# MATRIXMODULE.net
KiCad netlist of a schematic drawn in EAGLE
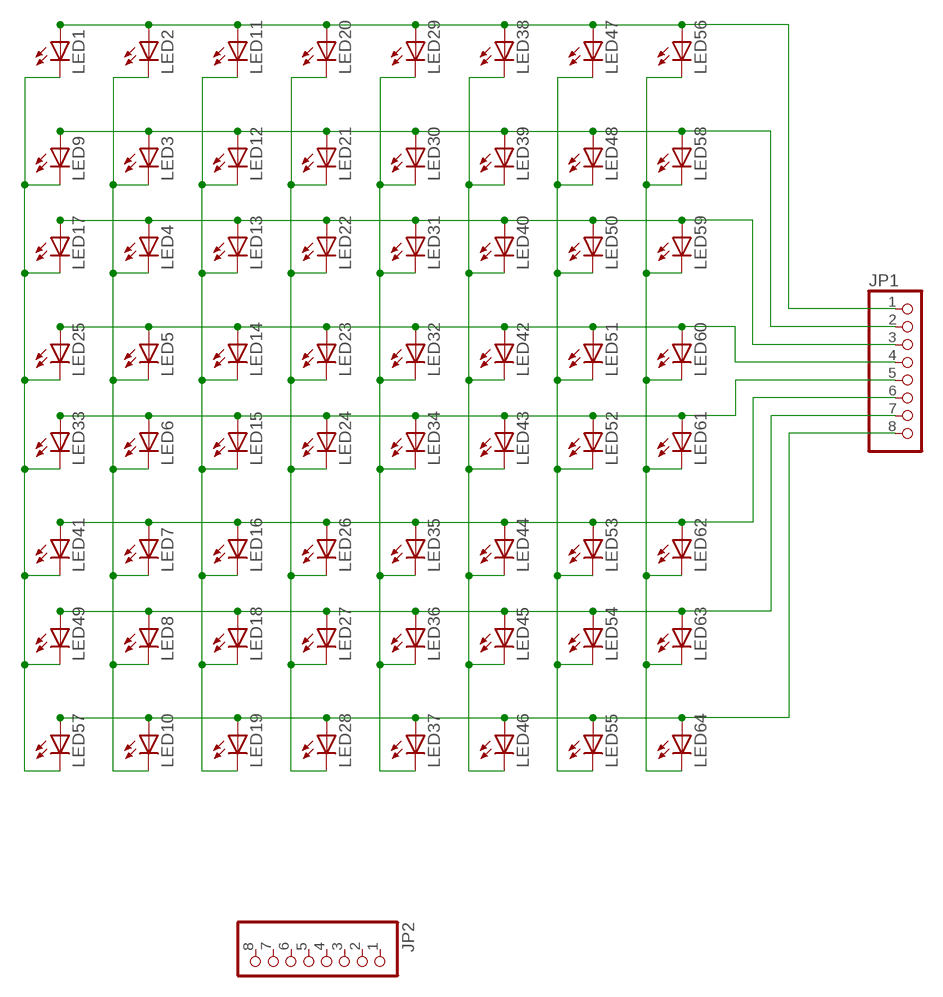
[diagram p0: schematic, sheet 1]

(export (version "E")
  (design (tool "Eeschema 10.0.6"))
  (components
    (comp (ref "JP1")
      (value "PINHD-1X8CLEANBIG")
      (footprint "eagle-import:1X08-CLEANBIG")
      (libsource (lib "eagle-import") (part "PINHD-1X8CLEANBIG"))
    )
    (comp (ref "JP2")
      (value "PINHD-1X8CLEANBIG")
      (footprint "eagle-import:1X08-CLEANBIG")
      (libsource (lib "eagle-import") (part "PINHD-1X8CLEANBIG"))
    )
    (comp (ref "LED1")
      (value "LED5MM")
      (footprint "eagle-import:LED5MM")
      (libsource (lib "eagle-import") (part "LED5MM"))
    )
    (comp (ref "LED2")
      (value "LED5MM")
      (footprint "eagle-import:LED5MM")
      (libsource (lib "eagle-import") (part "LED5MM"))
    )
    (comp (ref "LED3")
      (value "LED5MM")
      (footprint "eagle-import:LED5MM")
      (libsource (lib "eagle-import") (part "LED5MM"))
    )
    (comp (ref "LED4")
      (value "LED5MM")
      (footprint "eagle-import:LED5MM")
      (libsource (lib "eagle-import") (part "LED5MM"))
    )
    (comp (ref "LED5")
      (value "LED5MM")
      (footprint "eagle-import:LED5MM")
      (libsource (lib "eagle-import") (part "LED5MM"))
    )
    (comp (ref "LED6")
      (value "LED5MM")
      (footprint "eagle-import:LED5MM")
      (libsource (lib "eagle-import") (part "LED5MM"))
    )
    (comp (ref "LED7")
      (value "LED5MM")
      (footprint "eagle-import:LED5MM")
      (libsource (lib "eagle-import") (part "LED5MM"))
    )
    (comp (ref "LED8")
      (value "LED5MM")
      (footprint "eagle-import:LED5MM")
      (libsource (lib "eagle-import") (part "LED5MM"))
    )
    (comp (ref "LED9")
      (value "LED5MM")
      (footprint "eagle-import:LED5MM")
      (libsource (lib "eagle-import") (part "LED5MM"))
    )
    (comp (ref "LED10")
      (value "LED5MM")
      (footprint "eagle-import:LED5MM")
      (libsource (lib "eagle-import") (part "LED5MM"))
    )
    (comp (ref "LED11")
      (value "LED5MM")
      (footprint "eagle-import:LED5MM")
      (libsource (lib "eagle-import") (part "LED5MM"))
    )
    (comp (ref "LED12")
      (value "LED5MM")
      (footprint "eagle-import:LED5MM")
      (libsource (lib "eagle-import") (part "LED5MM"))
    )
    (comp (ref "LED13")
      (value "LED5MM")
      (footprint "eagle-import:LED5MM")
      (libsource (lib "eagle-import") (part "LED5MM"))
    )
    (comp (ref "LED14")
      (value "LED5MM")
      (footprint "eagle-import:LED5MM")
      (libsource (lib "eagle-import") (part "LED5MM"))
    )
    (comp (ref "LED15")
      (value "LED5MM")
      (footprint "eagle-import:LED5MM")
      (libsource (lib "eagle-import") (part "LED5MM"))
    )
    (comp (ref "LED16")
      (value "LED5MM")
      (footprint "eagle-import:LED5MM")
      (libsource (lib "eagle-import") (part "LED5MM"))
    )
    (comp (ref "LED17")
      (value "LED5MM")
      (footprint "eagle-import:LED5MM")
      (libsource (lib "eagle-import") (part "LED5MM"))
    )
    (comp (ref "LED18")
      (value "LED5MM")
      (footprint "eagle-import:LED5MM")
      (libsource (lib "eagle-import") (part "LED5MM"))
    )
    (comp (ref "LED19")
      (value "LED5MM")
      (footprint "eagle-import:LED5MM")
      (libsource (lib "eagle-import") (part "LED5MM"))
    )
    (comp (ref "LED20")
      (value "LED5MM")
      (footprint "eagle-import:LED5MM")
      (libsource (lib "eagle-import") (part "LED5MM"))
    )
    (comp (ref "LED21")
      (value "LED5MM")
      (footprint "eagle-import:LED5MM")
      (libsource (lib "eagle-import") (part "LED5MM"))
    )
    (comp (ref "LED22")
      (value "LED5MM")
      (footprint "eagle-import:LED5MM")
      (libsource (lib "eagle-import") (part "LED5MM"))
    )
    (comp (ref "LED23")
      (value "LED5MM")
      (footprint "eagle-import:LED5MM")
      (libsource (lib "eagle-import") (part "LED5MM"))
    )
    (comp (ref "LED24")
      (value "LED5MM")
      (footprint "eagle-import:LED5MM")
      (libsource (lib "eagle-import") (part "LED5MM"))
    )
    (comp (ref "LED25")
      (value "LED5MM")
      (footprint "eagle-import:LED5MM")
      (libsource (lib "eagle-import") (part "LED5MM"))
    )
    (comp (ref "LED26")
      (value "LED5MM")
      (footprint "eagle-import:LED5MM")
      (libsource (lib "eagle-import") (part "LED5MM"))
    )
    (comp (ref "LED27")
      (value "LED5MM")
      (footprint "eagle-import:LED5MM")
      (libsource (lib "eagle-import") (part "LED5MM"))
    )
    (comp (ref "LED28")
      (value "LED5MM")
      (footprint "eagle-import:LED5MM")
      (libsource (lib "eagle-import") (part "LED5MM"))
    )
    (comp (ref "LED29")
      (value "LED5MM")
      (footprint "eagle-import:LED5MM")
      (libsource (lib "eagle-import") (part "LED5MM"))
    )
    (comp (ref "LED30")
      (value "LED5MM")
      (footprint "eagle-import:LED5MM")
      (libsource (lib "eagle-import") (part "LED5MM"))
    )
    (comp (ref "LED31")
      (value "LED5MM")
      (footprint "eagle-import:LED5MM")
      (libsource (lib "eagle-import") (part "LED5MM"))
    )
    (comp (ref "LED32")
      (value "LED5MM")
      (footprint "eagle-import:LED5MM")
      (libsource (lib "eagle-import") (part "LED5MM"))
    )
    (comp (ref "LED33")
      (value "LED5MM")
      (footprint "eagle-import:LED5MM")
      (libsource (lib "eagle-import") (part "LED5MM"))
    )
    (comp (ref "LED34")
      (value "LED5MM")
      (footprint "eagle-import:LED5MM")
      (libsource (lib "eagle-import") (part "LED5MM"))
    )
    (comp (ref "LED35")
      (value "LED5MM")
      (footprint "eagle-import:LED5MM")
      (libsource (lib "eagle-import") (part "LED5MM"))
    )
    (comp (ref "LED36")
      (value "LED5MM")
      (footprint "eagle-import:LED5MM")
      (libsource (lib "eagle-import") (part "LED5MM"))
    )
    (comp (ref "LED37")
      (value "LED5MM")
      (footprint "eagle-import:LED5MM")
      (libsource (lib "eagle-import") (part "LED5MM"))
    )
    (comp (ref "LED38")
      (value "LED5MM")
      (footprint "eagle-import:LED5MM")
      (libsource (lib "eagle-import") (part "LED5MM"))
    )
    (comp (ref "LED39")
      (value "LED5MM")
      (footprint "eagle-import:LED5MM")
      (libsource (lib "eagle-import") (part "LED5MM"))
    )
    (comp (ref "LED40")
      (value "LED5MM")
      (footprint "eagle-import:LED5MM")
      (libsource (lib "eagle-import") (part "LED5MM"))
    )
    (comp (ref "LED41")
      (value "LED5MM")
      (footprint "eagle-import:LED5MM")
      (libsource (lib "eagle-import") (part "LED5MM"))
    )
    (comp (ref "LED42")
      (value "LED5MM")
      (footprint "eagle-import:LED5MM")
      (libsource (lib "eagle-import") (part "LED5MM"))
    )
    (comp (ref "LED43")
      (value "LED5MM")
      (footprint "eagle-import:LED5MM")
      (libsource (lib "eagle-import") (part "LED5MM"))
    )
    (comp (ref "LED44")
      (value "LED5MM")
      (footprint "eagle-import:LED5MM")
      (libsource (lib "eagle-import") (part "LED5MM"))
    )
    (comp (ref "LED45")
      (value "LED5MM")
      (footprint "eagle-import:LED5MM")
      (libsource (lib "eagle-import") (part "LED5MM"))
    )
    (comp (ref "LED46")
      (value "LED5MM")
      (footprint "eagle-import:LED5MM")
      (libsource (lib "eagle-import") (part "LED5MM"))
    )
    (comp (ref "LED47")
      (value "LED5MM")
      (footprint "eagle-import:LED5MM")
      (libsource (lib "eagle-import") (part "LED5MM"))
    )
    (comp (ref "LED48")
      (value "LED5MM")
      (footprint "eagle-import:LED5MM")
      (libsource (lib "eagle-import") (part "LED5MM"))
    )
    (comp (ref "LED49")
      (value "LED5MM")
      (footprint "eagle-import:LED5MM")
      (libsource (lib "eagle-import") (part "LED5MM"))
    )
    (comp (ref "LED50")
      (value "LED5MM")
      (footprint "eagle-import:LED5MM")
      (libsource (lib "eagle-import") (part "LED5MM"))
    )
    (comp (ref "LED51")
      (value "LED5MM")
      (footprint "eagle-import:LED5MM")
      (libsource (lib "eagle-import") (part "LED5MM"))
    )
    (comp (ref "LED52")
      (value "LED5MM")
      (footprint "eagle-import:LED5MM")
      (libsource (lib "eagle-import") (part "LED5MM"))
    )
    (comp (ref "LED53")
      (value "LED5MM")
      (footprint "eagle-import:LED5MM")
      (libsource (lib "eagle-import") (part "LED5MM"))
    )
    (comp (ref "LED54")
      (value "LED5MM")
      (footprint "eagle-import:LED5MM")
      (libsource (lib "eagle-import") (part "LED5MM"))
    )
    (comp (ref "LED55")
      (value "LED5MM")
      (footprint "eagle-import:LED5MM")
      (libsource (lib "eagle-import") (part "LED5MM"))
    )
    (comp (ref "LED56")
      (value "LED5MM")
      (footprint "eagle-import:LED5MM")
      (libsource (lib "eagle-import") (part "LED5MM"))
    )
    (comp (ref "LED57")
      (value "LED5MM")
      (footprint "eagle-import:LED5MM")
      (libsource (lib "eagle-import") (part "LED5MM"))
    )
    (comp (ref "LED58")
      (value "LED5MM")
      (footprint "eagle-import:LED5MM")
      (libsource (lib "eagle-import") (part "LED5MM"))
    )
    (comp (ref "LED59")
      (value "LED5MM")
      (footprint "eagle-import:LED5MM")
      (libsource (lib "eagle-import") (part "LED5MM"))
    )
    (comp (ref "LED60")
      (value "LED5MM")
      (footprint "eagle-import:LED5MM")
      (libsource (lib "eagle-import") (part "LED5MM"))
    )
    (comp (ref "LED61")
      (value "LED5MM")
      (footprint "eagle-import:LED5MM")
      (libsource (lib "eagle-import") (part "LED5MM"))
    )
    (comp (ref "LED62")
      (value "LED5MM")
      (footprint "eagle-import:LED5MM")
      (libsource (lib "eagle-import") (part "LED5MM"))
    )
    (comp (ref "LED63")
      (value "LED5MM")
      (footprint "eagle-import:LED5MM")
      (libsource (lib "eagle-import") (part "LED5MM"))
    )
    (comp (ref "LED64")
      (value "LED5MM")
      (footprint "eagle-import:LED5MM")
      (libsource (lib "eagle-import") (part "LED5MM"))
    )
  )
  (nets
    (net (code "1") (name "Net-(JP1-Pad1)") (class "Default")
      (node (ref "JP1") (pin "1") (pinfunction "1_1") (pintype "passive"))
      (node (ref "LED1") (pin "A") (pinfunction "A_A") (pintype "passive"))
      (node (ref "LED11") (pin "A") (pinfunction "A_A") (pintype "passive"))
      (node (ref "LED2") (pin "A") (pinfunction "A_A") (pintype "passive"))
      (node (ref "LED20") (pin "A") (pinfunction "A_A") (pintype "passive"))
      (node (ref "LED29") (pin "A") (pinfunction "A_A") (pintype "passive"))
      (node (ref "LED38") (pin "A") (pinfunction "A_A") (pintype "passive"))
      (node (ref "LED47") (pin "A") (pinfunction "A_A") (pintype "passive"))
      (node (ref "LED56") (pin "A") (pinfunction "A_A") (pintype "passive"))
    )
    (net (code "2") (name "Net-(JP1-Pad2)") (class "Default")
      (node (ref "JP1") (pin "2") (pinfunction "2_2") (pintype "passive"))
      (node (ref "LED12") (pin "A") (pinfunction "A_A") (pintype "passive"))
      (node (ref "LED21") (pin "A") (pinfunction "A_A") (pintype "passive"))
      (node (ref "LED3") (pin "A") (pinfunction "A_A") (pintype "passive"))
      (node (ref "LED30") (pin "A") (pinfunction "A_A") (pintype "passive"))
      (node (ref "LED39") (pin "A") (pinfunction "A_A") (pintype "passive"))
      (node (ref "LED48") (pin "A") (pinfunction "A_A") (pintype "passive"))
      (node (ref "LED58") (pin "A") (pinfunction "A_A") (pintype "passive"))
      (node (ref "LED9") (pin "A") (pinfunction "A_A") (pintype "passive"))
    )
    (net (code "3") (name "Net-(JP1-Pad3)") (class "Default")
      (node (ref "JP1") (pin "3") (pinfunction "3_3") (pintype "passive"))
      (node (ref "LED13") (pin "A") (pinfunction "A_A") (pintype "passive"))
      (node (ref "LED17") (pin "A") (pinfunction "A_A") (pintype "passive"))
      (node (ref "LED22") (pin "A") (pinfunction "A_A") (pintype "passive"))
      (node (ref "LED31") (pin "A") (pinfunction "A_A") (pintype "passive"))
      (node (ref "LED4") (pin "A") (pinfunction "A_A") (pintype "passive"))
      (node (ref "LED40") (pin "A") (pinfunction "A_A") (pintype "passive"))
      (node (ref "LED50") (pin "A") (pinfunction "A_A") (pintype "passive"))
      (node (ref "LED59") (pin "A") (pinfunction "A_A") (pintype "passive"))
    )
    (net (code "4") (name "Net-(JP1-Pad4)") (class "Default")
      (node (ref "JP1") (pin "4") (pinfunction "4_4") (pintype "passive"))
      (node (ref "LED14") (pin "A") (pinfunction "A_A") (pintype "passive"))
      (node (ref "LED23") (pin "A") (pinfunction "A_A") (pintype "passive"))
      (node (ref "LED25") (pin "A") (pinfunction "A_A") (pintype "passive"))
      (node (ref "LED32") (pin "A") (pinfunction "A_A") (pintype "passive"))
      (node (ref "LED42") (pin "A") (pinfunction "A_A") (pintype "passive"))
      (node (ref "LED5") (pin "A") (pinfunction "A_A") (pintype "passive"))
      (node (ref "LED51") (pin "A") (pinfunction "A_A") (pintype "passive"))
      (node (ref "LED60") (pin "A") (pinfunction "A_A") (pintype "passive"))
    )
    (net (code "5") (name "Net-(JP1-Pad5)") (class "Default")
      (node (ref "JP1") (pin "5") (pinfunction "5_5") (pintype "passive"))
      (node (ref "LED15") (pin "A") (pinfunction "A_A") (pintype "passive"))
      (node (ref "LED24") (pin "A") (pinfunction "A_A") (pintype "passive"))
      (node (ref "LED33") (pin "A") (pinfunction "A_A") (pintype "passive"))
      (node (ref "LED34") (pin "A") (pinfunction "A_A") (pintype "passive"))
      (node (ref "LED43") (pin "A") (pinfunction "A_A") (pintype "passive"))
      (node (ref "LED52") (pin "A") (pinfunction "A_A") (pintype "passive"))
      (node (ref "LED6") (pin "A") (pinfunction "A_A") (pintype "passive"))
      (node (ref "LED61") (pin "A") (pinfunction "A_A") (pintype "passive"))
    )
    (net (code "6") (name "Net-(JP1-Pad6)") (class "Default")
      (node (ref "JP1") (pin "6") (pinfunction "6_6") (pintype "passive"))
      (node (ref "LED16") (pin "A") (pinfunction "A_A") (pintype "passive"))
      (node (ref "LED26") (pin "A") (pinfunction "A_A") (pintype "passive"))
      (node (ref "LED35") (pin "A") (pinfunction "A_A") (pintype "passive"))
      (node (ref "LED41") (pin "A") (pinfunction "A_A") (pintype "passive"))
      (node (ref "LED44") (pin "A") (pinfunction "A_A") (pintype "passive"))
      (node (ref "LED53") (pin "A") (pinfunction "A_A") (pintype "passive"))
      (node (ref "LED62") (pin "A") (pinfunction "A_A") (pintype "passive"))
      (node (ref "LED7") (pin "A") (pinfunction "A_A") (pintype "passive"))
    )
    (net (code "7") (name "Net-(JP1-Pad7)") (class "Default")
      (node (ref "JP1") (pin "7") (pinfunction "7_7") (pintype "passive"))
      (node (ref "LED18") (pin "A") (pinfunction "A_A") (pintype "passive"))
      (node (ref "LED27") (pin "A") (pinfunction "A_A") (pintype "passive"))
      (node (ref "LED36") (pin "A") (pinfunction "A_A") (pintype "passive"))
      (node (ref "LED45") (pin "A") (pinfunction "A_A") (pintype "passive"))
      (node (ref "LED49") (pin "A") (pinfunction "A_A") (pintype "passive"))
      (node (ref "LED54") (pin "A") (pinfunction "A_A") (pintype "passive"))
      (node (ref "LED63") (pin "A") (pinfunction "A_A") (pintype "passive"))
      (node (ref "LED8") (pin "A") (pinfunction "A_A") (pintype "passive"))
    )
    (net (code "8") (name "Net-(JP1-Pad8)") (class "Default")
      (node (ref "JP1") (pin "8") (pinfunction "8_8") (pintype "passive"))
      (node (ref "LED10") (pin "A") (pinfunction "A_A") (pintype "passive"))
      (node (ref "LED19") (pin "A") (pinfunction "A_A") (pintype "passive"))
      (node (ref "LED28") (pin "A") (pinfunction "A_A") (pintype "passive"))
      (node (ref "LED37") (pin "A") (pinfunction "A_A") (pintype "passive"))
      (node (ref "LED46") (pin "A") (pinfunction "A_A") (pintype "passive"))
      (node (ref "LED55") (pin "A") (pinfunction "A_A") (pintype "passive"))
      (node (ref "LED57") (pin "A") (pinfunction "A_A") (pintype "passive"))
      (node (ref "LED64") (pin "A") (pinfunction "A_A") (pintype "passive"))
    )
    (net (code "9") (name "Net-(LED1-C)") (class "Default")
      (node (ref "LED1") (pin "K") (pinfunction "C_K") (pintype "passive"))
      (node (ref "LED17") (pin "K") (pinfunction "C_K") (pintype "passive"))
      (node (ref "LED25") (pin "K") (pinfunction "C_K") (pintype "passive"))
      (node (ref "LED33") (pin "K") (pinfunction "C_K") (pintype "passive"))
      (node (ref "LED41") (pin "K") (pinfunction "C_K") (pintype "passive"))
      (node (ref "LED49") (pin "K") (pinfunction "C_K") (pintype "passive"))
      (node (ref "LED57") (pin "K") (pinfunction "C_K") (pintype "passive"))
      (node (ref "LED9") (pin "K") (pinfunction "C_K") (pintype "passive"))
    )
    (net (code "10") (name "Net-(LED10-C)") (class "Default")
      (node (ref "LED10") (pin "K") (pinfunction "C_K") (pintype "passive"))
      (node (ref "LED2") (pin "K") (pinfunction "C_K") (pintype "passive"))
      (node (ref "LED3") (pin "K") (pinfunction "C_K") (pintype "passive"))
      (node (ref "LED4") (pin "K") (pinfunction "C_K") (pintype "passive"))
      (node (ref "LED5") (pin "K") (pinfunction "C_K") (pintype "passive"))
      (node (ref "LED6") (pin "K") (pinfunction "C_K") (pintype "passive"))
      (node (ref "LED7") (pin "K") (pinfunction "C_K") (pintype "passive"))
      (node (ref "LED8") (pin "K") (pinfunction "C_K") (pintype "passive"))
    )
    (net (code "11") (name "Net-(LED11-C)") (class "Default")
      (node (ref "LED11") (pin "K") (pinfunction "C_K") (pintype "passive"))
      (node (ref "LED12") (pin "K") (pinfunction "C_K") (pintype "passive"))
      (node (ref "LED13") (pin "K") (pinfunction "C_K") (pintype "passive"))
      (node (ref "LED14") (pin "K") (pinfunction "C_K") (pintype "passive"))
      (node (ref "LED15") (pin "K") (pinfunction "C_K") (pintype "passive"))
      (node (ref "LED16") (pin "K") (pinfunction "C_K") (pintype "passive"))
      (node (ref "LED18") (pin "K") (pinfunction "C_K") (pintype "passive"))
      (node (ref "LED19") (pin "K") (pinfunction "C_K") (pintype "passive"))
    )
    (net (code "12") (name "Net-(LED20-C)") (class "Default")
      (node (ref "LED20") (pin "K") (pinfunction "C_K") (pintype "passive"))
      (node (ref "LED21") (pin "K") (pinfunction "C_K") (pintype "passive"))
      (node (ref "LED22") (pin "K") (pinfunction "C_K") (pintype "passive"))
      (node (ref "LED23") (pin "K") (pinfunction "C_K") (pintype "passive"))
      (node (ref "LED24") (pin "K") (pinfunction "C_K") (pintype "passive"))
      (node (ref "LED26") (pin "K") (pinfunction "C_K") (pintype "passive"))
      (node (ref "LED27") (pin "K") (pinfunction "C_K") (pintype "passive"))
      (node (ref "LED28") (pin "K") (pinfunction "C_K") (pintype "passive"))
    )
    (net (code "13") (name "Net-(LED29-C)") (class "Default")
      (node (ref "LED29") (pin "K") (pinfunction "C_K") (pintype "passive"))
      (node (ref "LED30") (pin "K") (pinfunction "C_K") (pintype "passive"))
      (node (ref "LED31") (pin "K") (pinfunction "C_K") (pintype "passive"))
      (node (ref "LED32") (pin "K") (pinfunction "C_K") (pintype "passive"))
      (node (ref "LED34") (pin "K") (pinfunction "C_K") (pintype "passive"))
      (node (ref "LED35") (pin "K") (pinfunction "C_K") (pintype "passive"))
      (node (ref "LED36") (pin "K") (pinfunction "C_K") (pintype "passive"))
      (node (ref "LED37") (pin "K") (pinfunction "C_K") (pintype "passive"))
    )
    (net (code "14") (name "Net-(LED38-C)") (class "Default")
      (node (ref "LED38") (pin "K") (pinfunction "C_K") (pintype "passive"))
      (node (ref "LED39") (pin "K") (pinfunction "C_K") (pintype "passive"))
      (node (ref "LED40") (pin "K") (pinfunction "C_K") (pintype "passive"))
      (node (ref "LED42") (pin "K") (pinfunction "C_K") (pintype "passive"))
      (node (ref "LED43") (pin "K") (pinfunction "C_K") (pintype "passive"))
      (node (ref "LED44") (pin "K") (pinfunction "C_K") (pintype "passive"))
      (node (ref "LED45") (pin "K") (pinfunction "C_K") (pintype "passive"))
      (node (ref "LED46") (pin "K") (pinfunction "C_K") (pintype "passive"))
    )
    (net (code "15") (name "Net-(LED47-C)") (class "Default")
      (node (ref "LED47") (pin "K") (pinfunction "C_K") (pintype "passive"))
      (node (ref "LED48") (pin "K") (pinfunction "C_K") (pintype "passive"))
      (node (ref "LED50") (pin "K") (pinfunction "C_K") (pintype "passive"))
      (node (ref "LED51") (pin "K") (pinfunction "C_K") (pintype "passive"))
      (node (ref "LED52") (pin "K") (pinfunction "C_K") (pintype "passive"))
      (node (ref "LED53") (pin "K") (pinfunction "C_K") (pintype "passive"))
      (node (ref "LED54") (pin "K") (pinfunction "C_K") (pintype "passive"))
      (node (ref "LED55") (pin "K") (pinfunction "C_K") (pintype "passive"))
    )
    (net (code "16") (name "Net-(LED56-C)") (class "Default")
      (node (ref "LED56") (pin "K") (pinfunction "C_K") (pintype "passive"))
      (node (ref "LED58") (pin "K") (pinfunction "C_K") (pintype "passive"))
      (node (ref "LED59") (pin "K") (pinfunction "C_K") (pintype "passive"))
      (node (ref "LED60") (pin "K") (pinfunction "C_K") (pintype "passive"))
      (node (ref "LED61") (pin "K") (pinfunction "C_K") (pintype "passive"))
      (node (ref "LED62") (pin "K") (pinfunction "C_K") (pintype "passive"))
      (node (ref "LED63") (pin "K") (pinfunction "C_K") (pintype "passive"))
      (node (ref "LED64") (pin "K") (pinfunction "C_K") (pintype "passive"))
    )
    (net (code "17") (name "unconnected-(JP2-Pad1)") (class "Default")
      (node (ref "JP2") (pin "1") (pinfunction "1_1") (pintype "passive"))
    )
    (net (code "18") (name "unconnected-(JP2-Pad2)") (class "Default")
      (node (ref "JP2") (pin "2") (pinfunction "2_2") (pintype "passive"))
    )
    (net (code "19") (name "unconnected-(JP2-Pad3)") (class "Default")
      (node (ref "JP2") (pin "3") (pinfunction "3_3") (pintype "passive"))
    )
    (net (code "20") (name "unconnected-(JP2-Pad4)") (class "Default")
      (node (ref "JP2") (pin "4") (pinfunction "4_4") (pintype "passive"))
    )
    (net (code "21") (name "unconnected-(JP2-Pad5)") (class "Default")
      (node (ref "JP2") (pin "5") (pinfunction "5_5") (pintype "passive"))
    )
    (net (code "22") (name "unconnected-(JP2-Pad6)") (class "Default")
      (node (ref "JP2") (pin "6") (pinfunction "6_6") (pintype "passive"))
    )
    (net (code "23") (name "unconnected-(JP2-Pad7)") (class "Default")
      (node (ref "JP2") (pin "7") (pinfunction "7_7") (pintype "passive"))
    )
    (net (code "24") (name "unconnected-(JP2-Pad8)") (class "Default")
      (node (ref "JP2") (pin "8") (pinfunction "8_8") (pintype "passive"))
    )
  )
)
